# Part09_Config.net
KiCad netlist of a schematic drawn in Altium Designer
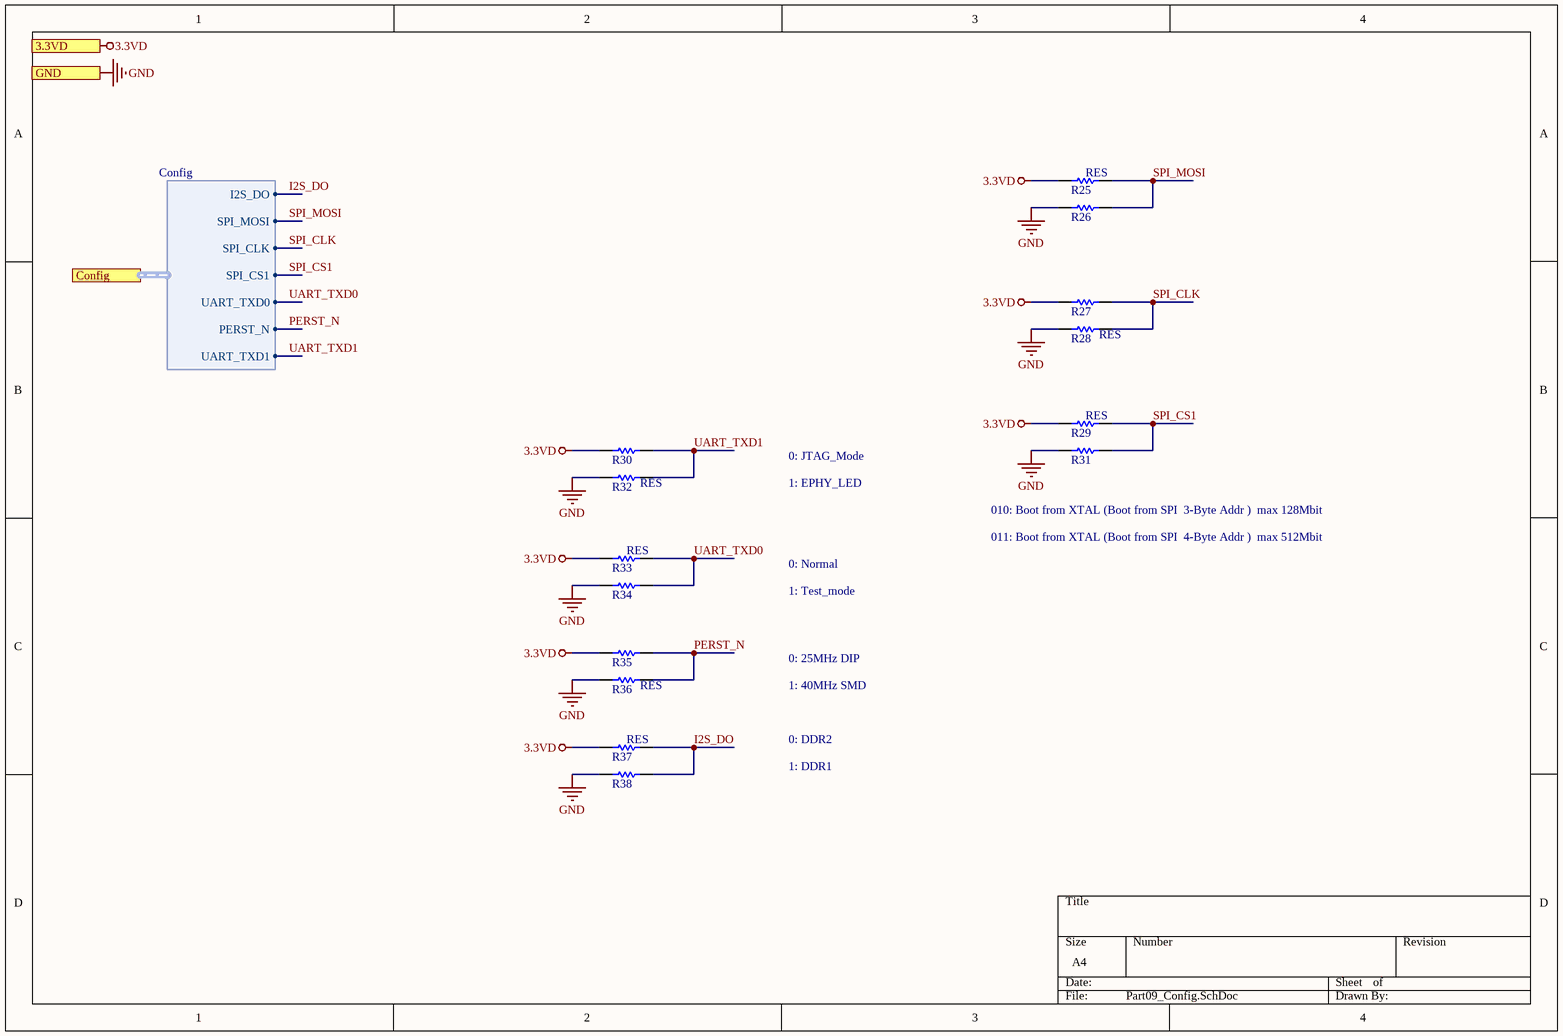
[diagram p0: Part09_Config.SchDoc]

(export (version "E")
  (design (tool "Eeschema 10.0.6"))
  (components
    (comp (ref "R25") (value "RES") (footprint "0402R") (libsource (lib "电阻") (part "RES")))
    (comp (ref "R26") (value "RES") (footprint "0402R") (libsource (lib "电阻") (part "RES")))
    (comp (ref "R27") (value "RES") (footprint "0402R") (libsource (lib "电阻") (part "RES")))
    (comp (ref "R28") (value "RES") (footprint "0402R") (libsource (lib "电阻") (part "RES")))
    (comp (ref "R29") (value "RES") (footprint "0402R") (libsource (lib "电阻") (part "RES")))
    (comp (ref "R30") (value "RES") (footprint "0402R") (libsource (lib "电阻") (part "RES")))
    (comp (ref "R31") (value "RES") (footprint "0402R") (libsource (lib "电阻") (part "RES")))
    (comp (ref "R32") (value "RES") (footprint "0402R") (libsource (lib "电阻") (part "RES")))
    (comp (ref "R33") (value "RES") (footprint "0402R") (libsource (lib "电阻") (part "RES")))
    (comp (ref "R34") (value "RES") (footprint "0402R") (libsource (lib "电阻") (part "RES")))
    (comp (ref "R35") (value "RES") (footprint "0402R") (libsource (lib "电阻") (part "RES")))
    (comp (ref "R36") (value "RES") (footprint "0402R") (libsource (lib "电阻") (part "RES")))
    (comp (ref "R37") (value "RES") (footprint "0402R") (libsource (lib "电阻") (part "RES")))
    (comp (ref "R38") (value "RES") (footprint "0402R") (libsource (lib "电阻") (part "RES")))
  )
  (nets
    (net (code "2") (name "/I2S_DO") (class "Default")
      (node (ref "R37") (pin "2") (pinfunction "2_2") (pintype "passive"))
      (node (ref "R38") (pin "2") (pinfunction "2_2") (pintype "passive"))
    )
    (net (code "3") (name "/PERST_N") (class "Default")
      (node (ref "R35") (pin "2") (pinfunction "2_2") (pintype "passive"))
      (node (ref "R36") (pin "2") (pinfunction "2_2") (pintype "passive"))
    )
    (net (code "4") (name "/SPI_CLK") (class "Default")
      (node (ref "R27") (pin "2") (pinfunction "2_2") (pintype "passive"))
      (node (ref "R28") (pin "2") (pinfunction "2_2") (pintype "passive"))
    )
    (net (code "5") (name "/SPI_CS1") (class "Default")
      (node (ref "R29") (pin "2") (pinfunction "2_2") (pintype "passive"))
      (node (ref "R31") (pin "2") (pinfunction "2_2") (pintype "passive"))
    )
    (net (code "6") (name "/SPI_MOSI") (class "Default")
      (node (ref "R25") (pin "2") (pinfunction "2_2") (pintype "passive"))
      (node (ref "R26") (pin "2") (pinfunction "2_2") (pintype "passive"))
    )
    (net (code "7") (name "/UART_TXD0") (class "Default")
      (node (ref "R33") (pin "2") (pinfunction "2_2") (pintype "passive"))
      (node (ref "R34") (pin "2") (pinfunction "2_2") (pintype "passive"))
    )
    (net (code "8") (name "/UART_TXD1") (class "Default")
      (node (ref "R30") (pin "2") (pinfunction "2_2") (pintype "passive"))
      (node (ref "R32") (pin "2") (pinfunction "2_2") (pintype "passive"))
    )
    (net (code "10") (name "3.3VD") (class "Default")
      (node (ref "R25") (pin "1") (pinfunction "1_1") (pintype "passive"))
      (node (ref "R27") (pin "1") (pinfunction "1_1") (pintype "passive"))
      (node (ref "R29") (pin "1") (pinfunction "1_1") (pintype "passive"))
      (node (ref "R30") (pin "1") (pinfunction "1_1") (pintype "passive"))
      (node (ref "R33") (pin "1") (pinfunction "1_1") (pintype "passive"))
      (node (ref "R35") (pin "1") (pinfunction "1_1") (pintype "passive"))
      (node (ref "R37") (pin "1") (pinfunction "1_1") (pintype "passive"))
    )
    (net (code "11") (name "GND") (class "Default")
      (node (ref "R26") (pin "1") (pinfunction "1_1") (pintype "passive"))
      (node (ref "R28") (pin "1") (pinfunction "1_1") (pintype "passive"))
      (node (ref "R31") (pin "1") (pinfunction "1_1") (pintype "passive"))
      (node (ref "R32") (pin "1") (pinfunction "1_1") (pintype "passive"))
      (node (ref "R34") (pin "1") (pinfunction "1_1") (pintype "passive"))
      (node (ref "R36") (pin "1") (pinfunction "1_1") (pintype "passive"))
      (node (ref "R38") (pin "1") (pinfunction "1_1") (pintype "passive"))
    )
  )
)
